# Schematic.net
KiCad netlist of a schematic drawn in Altium Designer
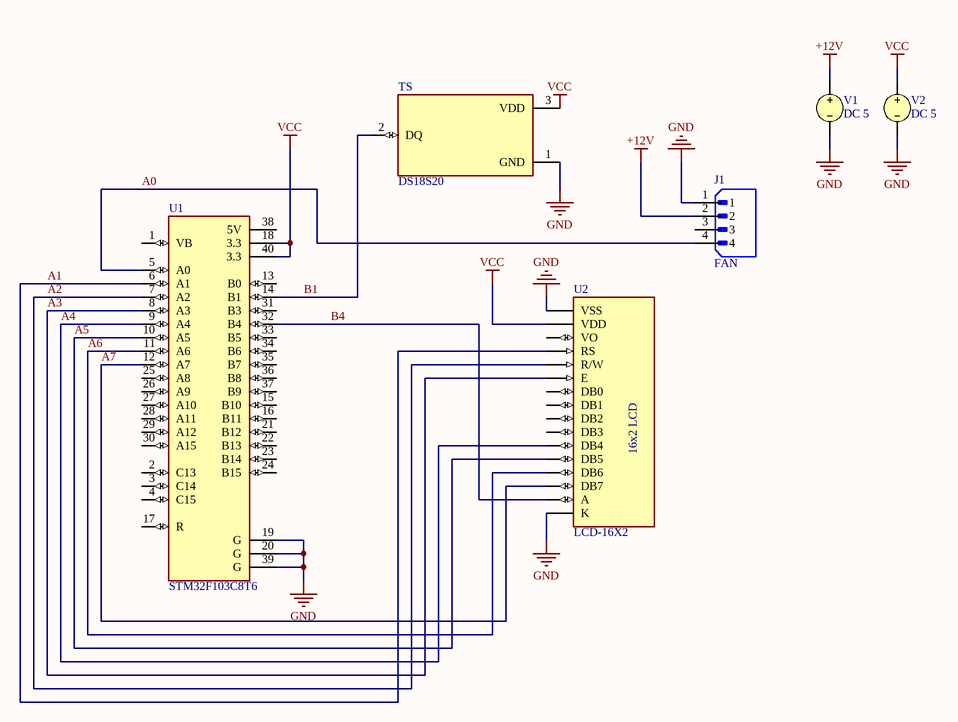
[diagram p0: Schematic.SchDoc]

(export (version "E")
  (design (tool "Eeschema 10.0.6"))
  (components
    (comp (ref "J1")
      (value "FAN")
      (footprint "JST_B4B-XH-A(LF)(SN)")
      (description "Connector Header Through Hole 4 position 0.098 (2.50mm)")
      (fields (field (name "MF") "JST Sales") (field (name "MP") "B4B-XH-A(LF)(SN)"))
      (libsource (lib "B4B-XH-A(LF)(SN)") (part "B4B-XH-A(LF)(SN)"))
    )
    (comp (ref "TS")
      (value "DS18S20")
      (footprint "TO92127P495H695-3:TO92127P495H695-3")
      (description "Temperature Sensor Digital, Local -55Â°C ~ 125Â°C 9 b TO-92-3")
      (fields (field (name "MF") "Maxim Integrated"))
      (libsource (lib "DS18S20+") (part "DS18S20+"))
    )
    (comp (ref "U1")
      (value "STM32F103C8T6")
      (footprint "MODULE_ZC323000:MODULE_ZC323000")
      (description "STM32F103C8T6 ARM STM32 Minimum System Development Board Module For Arduino")
      (fields (field (name "MP") "ZC323000"))
      (libsource (lib "ZC323000") (part "ZC323000"))
    )
    (comp (ref "U2")
      (value "LCD-16X2")
      (footprint "MODULE_LCD-16X2")
      (description "Display Development Tools 16x2 Black on Green Char LCD w Backlight")
      (fields (field (name "MF") "Gravitech"))
      (libsource (lib "LCD-16X2") (part "LCD-16X2"))
    )
    (comp (ref "V1")
      (value "DC 5")
      (description "Voltage Source")
      (fields (field (name "PUBLISHER") "Altium Limited"))
      (libsource (lib "Simulation Generic Components") (part "VSRC"))
    )
    (comp (ref "V2")
      (value "DC 5")
      (description "Voltage Source")
      (fields (field (name "PUBLISHER") "Altium Limited"))
      (libsource (lib "Simulation Generic Components") (part "VSRC"))
    )
  )
  (nets
    (net (code "1") (name "+12V") (class "Default")
      (node (ref "J1") (pin "2") (pinfunction "2_2") (pintype "power_in"))
      (node (ref "V1") (pin "1") (pinfunction "1_1") (pintype "passive"))
    )
    (net (code "2") (name "/A0") (class "Default")
      (node (ref "J1") (pin "4") (pinfunction "4_4") (pintype "passive"))
      (node (ref "U1") (pin "5") (pinfunction "A0_5") (pintype "bidirectional"))
    )
    (net (code "3") (name "/A1") (class "Default")
      (node (ref "U1") (pin "6") (pinfunction "A1_6") (pintype "bidirectional"))
      (node (ref "U2") (pin "4") (pinfunction "RS_4") (pintype "input"))
    )
    (net (code "4") (name "/A2") (class "Default")
      (node (ref "U1") (pin "7") (pinfunction "A2_7") (pintype "bidirectional"))
      (node (ref "U2") (pin "5") (pinfunction "R/W_5") (pintype "input"))
    )
    (net (code "5") (name "/A3") (class "Default")
      (node (ref "U1") (pin "8") (pinfunction "A3_8") (pintype "bidirectional"))
      (node (ref "U2") (pin "6") (pinfunction "E_6") (pintype "input"))
    )
    (net (code "6") (name "/A4") (class "Default")
      (node (ref "U1") (pin "9") (pinfunction "A4_9") (pintype "bidirectional"))
      (node (ref "U2") (pin "11") (pinfunction "DB4_11") (pintype "bidirectional"))
    )
    (net (code "7") (name "/A5") (class "Default")
      (node (ref "U1") (pin "10") (pinfunction "A5_10") (pintype "bidirectional"))
      (node (ref "U2") (pin "12") (pinfunction "DB5_12") (pintype "bidirectional"))
    )
    (net (code "8") (name "/A6") (class "Default")
      (node (ref "U1") (pin "11") (pinfunction "A6_11") (pintype "bidirectional"))
      (node (ref "U2") (pin "13") (pinfunction "DB6_13") (pintype "bidirectional"))
    )
    (net (code "9") (name "/A7") (class "Default")
      (node (ref "U1") (pin "12") (pinfunction "A7_12") (pintype "bidirectional"))
      (node (ref "U2") (pin "14") (pinfunction "DB7_14") (pintype "bidirectional"))
    )
    (net (code "10") (name "/B1") (class "Default")
      (node (ref "TS") (pin "2") (pinfunction "DQ_2") (pintype "bidirectional"))
      (node (ref "U1") (pin "14") (pinfunction "B1_14") (pintype "bidirectional"))
    )
    (net (code "11") (name "/B4") (class "Default")
      (node (ref "U1") (pin "32") (pinfunction "B4_32") (pintype "bidirectional"))
      (node (ref "U2") (pin "15") (pinfunction "A_15") (pintype "bidirectional"))
    )
    (net (code "12") (name "GND") (class "Default")
      (node (ref "J1") (pin "1") (pinfunction "1_1") (pintype "passive"))
      (node (ref "TS") (pin "1") (pinfunction "GND_1") (pintype "power_in"))
      (node (ref "U1") (pin "19") (pinfunction "G_19") (pintype "power_in"))
      (node (ref "U1") (pin "20") (pinfunction "G_20") (pintype "power_in"))
      (node (ref "U1") (pin "39") (pinfunction "G_39") (pintype "power_in"))
      (node (ref "U2") (pin "1") (pinfunction "VSS_1") (pintype "power_in"))
      (node (ref "U2") (pin "16") (pinfunction "K_16") (pintype "power_in"))
      (node (ref "V1") (pin "2") (pinfunction "2_2") (pintype "passive"))
      (node (ref "V2") (pin "2") (pinfunction "2_2") (pintype "passive"))
    )
    (net (code "13") (name "VCC") (class "Default")
      (node (ref "TS") (pin "3") (pinfunction "VDD_3") (pintype "power_in"))
      (node (ref "U1") (pin "18") (pinfunction "3.3_18") (pintype "power_in"))
      (node (ref "U1") (pin "40") (pinfunction "3.3_40") (pintype "power_in"))
      (node (ref "U2") (pin "2") (pinfunction "VDD_2") (pintype "power_in"))
      (node (ref "V2") (pin "1") (pinfunction "1_1") (pintype "passive"))
    )
    (net (code "14") (name "unconnected-(J1-Pad3)") (class "Default")
      (node (ref "J1") (pin "3") (pinfunction "3_3") (pintype "passive"))
    )
    (net (code "15") (name "unconnected-(U1-5V-Pad38)") (class "Default")
      (node (ref "U1") (pin "38") (pinfunction "5V_38") (pintype "power_in"))
    )
    (net (code "16") (name "unconnected-(U1-A8-Pad25)") (class "Default")
      (node (ref "U1") (pin "25") (pinfunction "A8_25") (pintype "bidirectional"))
    )
    (net (code "17") (name "unconnected-(U1-A9-Pad26)") (class "Default")
      (node (ref "U1") (pin "26") (pinfunction "A9_26") (pintype "bidirectional"))
    )
    (net (code "18") (name "unconnected-(U1-A10-Pad27)") (class "Default")
      (node (ref "U1") (pin "27") (pinfunction "A10_27") (pintype "bidirectional"))
    )
    (net (code "19") (name "unconnected-(U1-A11-Pad28)") (class "Default")
      (node (ref "U1") (pin "28") (pinfunction "A11_28") (pintype "bidirectional"))
    )
    (net (code "20") (name "unconnected-(U1-A12-Pad29)") (class "Default")
      (node (ref "U1") (pin "29") (pinfunction "A12_29") (pintype "bidirectional"))
    )
    (net (code "21") (name "unconnected-(U1-A15-Pad30)") (class "Default")
      (node (ref "U1") (pin "30") (pinfunction "A15_30") (pintype "bidirectional"))
    )
    (net (code "22") (name "unconnected-(U1-B0-Pad13)") (class "Default")
      (node (ref "U1") (pin "13") (pinfunction "B0_13") (pintype "bidirectional"))
    )
    (net (code "23") (name "unconnected-(U1-B3-Pad31)") (class "Default")
      (node (ref "U1") (pin "31") (pinfunction "B3_31") (pintype "bidirectional"))
    )
    (net (code "24") (name "unconnected-(U1-B5-Pad33)") (class "Default")
      (node (ref "U1") (pin "33") (pinfunction "B5_33") (pintype "bidirectional"))
    )
    (net (code "25") (name "unconnected-(U1-B6-Pad34)") (class "Default")
      (node (ref "U1") (pin "34") (pinfunction "B6_34") (pintype "bidirectional"))
    )
    (net (code "26") (name "unconnected-(U1-B7-Pad35)") (class "Default")
      (node (ref "U1") (pin "35") (pinfunction "B7_35") (pintype "bidirectional"))
    )
    (net (code "27") (name "unconnected-(U1-B8-Pad36)") (class "Default")
      (node (ref "U1") (pin "36") (pinfunction "B8_36") (pintype "bidirectional"))
    )
    (net (code "28") (name "unconnected-(U1-B9-Pad37)") (class "Default")
      (node (ref "U1") (pin "37") (pinfunction "B9_37") (pintype "bidirectional"))
    )
    (net (code "29") (name "unconnected-(U1-B10-Pad15)") (class "Default")
      (node (ref "U1") (pin "15") (pinfunction "B10_15") (pintype "bidirectional"))
    )
    (net (code "30") (name "unconnected-(U1-B11-Pad16)") (class "Default")
      (node (ref "U1") (pin "16") (pinfunction "B11_16") (pintype "bidirectional"))
    )
    (net (code "31") (name "unconnected-(U1-B12-Pad21)") (class "Default")
      (node (ref "U1") (pin "21") (pinfunction "B12_21") (pintype "bidirectional"))
    )
    (net (code "32") (name "unconnected-(U1-B13-Pad22)") (class "Default")
      (node (ref "U1") (pin "22") (pinfunction "B13_22") (pintype "bidirectional"))
    )
    (net (code "33") (name "unconnected-(U1-B14-Pad23)") (class "Default")
      (node (ref "U1") (pin "23") (pinfunction "B14_23") (pintype "bidirectional"))
    )
    (net (code "34") (name "unconnected-(U1-B15-Pad24)") (class "Default")
      (node (ref "U1") (pin "24") (pinfunction "B15_24") (pintype "bidirectional"))
    )
    (net (code "35") (name "unconnected-(U1-C13-Pad2)") (class "Default")
      (node (ref "U1") (pin "2") (pinfunction "C13_2") (pintype "bidirectional"))
    )
    (net (code "36") (name "unconnected-(U1-C14-Pad3)") (class "Default")
      (node (ref "U1") (pin "3") (pinfunction "C14_3") (pintype "bidirectional"))
    )
    (net (code "37") (name "unconnected-(U1-C15-Pad4)") (class "Default")
      (node (ref "U1") (pin "4") (pinfunction "C15_4") (pintype "bidirectional"))
    )
    (net (code "38") (name "unconnected-(U1-R-Pad17)") (class "Default")
      (node (ref "U1") (pin "17") (pinfunction "R_17") (pintype "bidirectional"))
    )
    (net (code "39") (name "unconnected-(U1-VB-Pad1)") (class "Default")
      (node (ref "U1") (pin "1") (pinfunction "VB_1") (pintype "bidirectional"))
    )
    (net (code "40") (name "unconnected-(U2-DB0-Pad7)") (class "Default")
      (node (ref "U2") (pin "7") (pinfunction "DB0_7") (pintype "bidirectional"))
    )
    (net (code "41") (name "unconnected-(U2-DB1-Pad8)") (class "Default")
      (node (ref "U2") (pin "8") (pinfunction "DB1_8") (pintype "bidirectional"))
    )
    (net (code "42") (name "unconnected-(U2-DB2-Pad9)") (class "Default")
      (node (ref "U2") (pin "9") (pinfunction "DB2_9") (pintype "bidirectional"))
    )
    (net (code "43") (name "unconnected-(U2-DB3-Pad10)") (class "Default")
      (node (ref "U2") (pin "10") (pinfunction "DB3_10") (pintype "bidirectional"))
    )
    (net (code "44") (name "unconnected-(U2-VO-Pad3)") (class "Default")
      (node (ref "U2") (pin "3") (pinfunction "VO_3") (pintype "bidirectional"))
    )
  )
)
